# Power.net
KiCad netlist of a schematic drawn in Altium Designer
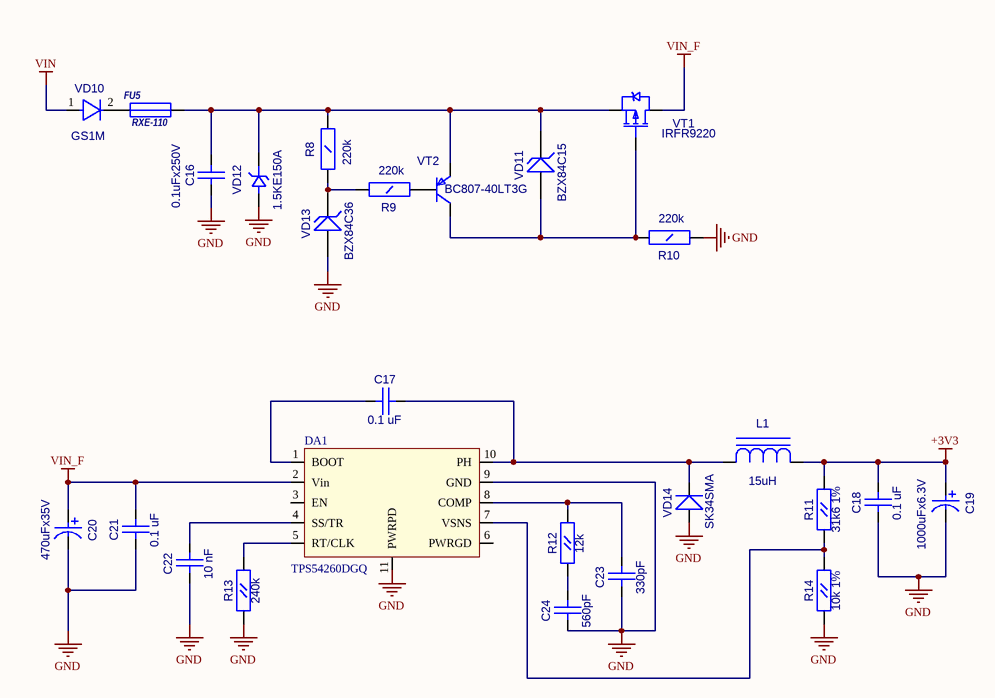
[diagram p0: Power.SchDoc]

(export (version "E")
  (design (tool "Eeschema 10.0.6"))
  (components
    (comp (ref "C16")
      (value "0.1uFx250V")
      (footprint "CC1206")
      (description "CC1206")
      (libsource (lib "gprs_modem_2") (part "CC1206"))
    )
    (comp (ref "C17")
      (value "0.1 uF")
      (footprint "CC0603")
      (description "CC0603")
      (libsource (lib "gprs_modem_2") (part "CC0603"))
    )
    (comp (ref "C18")
      (value "0.1 uF")
      (footprint "CC0603")
      (description "CC0603")
      (libsource (lib "gprs_modem_2") (part "CC0603"))
    )
    (comp (ref "C19")
      (value "1000uFx6.3V")
      (footprint "CC8X3.5")
      (description "CAP0.35")
      (libsource (lib "gprs_modem_2") (part "CAP0.35"))
    )
    (comp (ref "C20")
      (value "470uFx35V")
      (footprint "CC16X10_CAP0.5(1)(Primary)")
      (description "CAP0.5(1)")
      (libsource (lib "gprs_modem_2") (part "CAP0.5(1)"))
    )
    (comp (ref "C21")
      (value "0.1 uF")
      (footprint "CC0603")
      (description "CC0603")
      (libsource (lib "gprs_modem_2") (part "CC0603"))
    )
    (comp (ref "C22")
      (value "10 nF")
      (footprint "CC0603")
      (description "CC0603")
      (libsource (lib "gprs_modem_2") (part "CC0603"))
    )
    (comp (ref "C23")
      (value "330pF")
      (footprint "CC0603")
      (description "CC0603")
      (libsource (lib "gprs_modem_2") (part "CC0603"))
    )
    (comp (ref "C24")
      (value "560pF")
      (footprint "CC0603")
      (description "CC0603")
      (libsource (lib "gprs_modem_2") (part "CC0603"))
    )
    (comp (ref "DA1")
      (value "TPS54260DGQ")
      (footprint "S-PDSO-G10")
      (libsource (lib "gprs_modem") (part "TPS54260DGQ"))
    )
    (comp (ref "FU5")
      (value "RXE-110")
      (footprint "RXE-110")
      (libsource (lib "gprs_modem_2") (part "RXE-110"))
    )
    (comp (ref "L1")
      (value "15uH")
      (footprint "SDR0805")
      (description "SDR0805")
      (libsource (lib "gprs_modem") (part "SDR0805"))
    )
    (comp (ref "R8")
      (value "220k")
      (footprint "RC1206")
      (description "RC1206")
      (libsource (lib "gprs_modem_2") (part "RC1206"))
    )
    (comp (ref "R9")
      (value "220k")
      (footprint "RC1206")
      (description "RC1206")
      (libsource (lib "gprs_modem_2") (part "RC1206"))
    )
    (comp (ref "R10")
      (value "220k")
      (footprint "RC1206")
      (description "RC1206")
      (libsource (lib "gprs_modem_2") (part "RC1206"))
    )
    (comp (ref "R11")
      (value "31k6 1%")
      (footprint "RC0603")
      (description "RC0603")
      (libsource (lib "gprs_modem_2") (part "RC0603"))
    )
    (comp (ref "R12")
      (value "12k")
      (footprint "RC0603")
      (description "RC0603")
      (libsource (lib "gprs_modem_2") (part "RC0603"))
    )
    (comp (ref "R13")
      (value "240k")
      (footprint "RC0603")
      (description "RC0603")
      (libsource (lib "gprs_modem_2") (part "RC0603"))
    )
    (comp (ref "R14")
      (value "10k 1%")
      (footprint "RC0603")
      (description "RC0603")
      (libsource (lib "gprs_modem_2") (part "RC0603"))
    )
    (comp (ref "VD10") (value "GS1M") (footprint "SMA") (libsource (lib "Schetchik") (part "GS1M")))
    (comp (ref "VD11")
      (value "BZX84C15")
      (footprint "SOT-23(123)")
      (description "Zener Voltage Regulator Diode")
      (libsource (lib "gprs_modem_2") (part "BZX84"))
    )
    (comp (ref "VD12")
      (value "1.5KE150A")
      (footprint "DO-201")
      (description "1.5KE")
      (libsource (lib "gprs_modem") (part "1.5KE"))
    )
    (comp (ref "VD13")
      (value "BZX84C36")
      (footprint "SOT-23(123)")
      (description "Zener Voltage Regulator Diode")
      (libsource (lib "gprs_modem_2") (part "BZX84"))
    )
    (comp (ref "VD14")
      (value "SK34SMA")
      (footprint "SMA")
      (description "Schottky Rectifier")
      (libsource (lib "gprs_modem") (part "SK34SMA"))
    )
    (comp (ref "VT1")
      (value "IRFR9220")
      (footprint "D-PAK(TO-252AA)")
      (description "HEXFET Power MOSFET")
      (libsource (lib "gprs_modem") (part "IRFR9220"))
    )
    (comp (ref "VT2")
      (value "BC807-40LT3G")
      (footprint "SOT-23(123)")
      (description "BC856B")
      (libsource (lib "Schetchik") (part "BC856B"))
    )
  )
  (nets
    (net (code "1") (name "+3V3") (class "Default")
      (node (ref "C18") (pin "1") (pinfunction "A_1") (pintype "passive"))
      (node (ref "C19") (pin "1") (pintype "passive"))
      (node (ref "L1") (pin "2") (pinfunction "A_2") (pintype "passive"))
      (node (ref "R11") (pin "2") (pinfunction "B_2") (pintype "passive"))
    )
    (net (code "2") (name "GND") (class "Default")
      (node (ref "C16") (pin "1") (pinfunction "A_1") (pintype "passive"))
      (node (ref "C18") (pin "2") (pinfunction "B_2") (pintype "passive"))
      (node (ref "C19") (pin "2") (pintype "passive"))
      (node (ref "C20") (pin "1") (pintype "passive"))
      (node (ref "C21") (pin "2") (pinfunction "B_2") (pintype "passive"))
      (node (ref "C22") (pin "2") (pinfunction "B_2") (pintype "passive"))
      (node (ref "C23") (pin "2") (pinfunction "B_2") (pintype "passive"))
      (node (ref "C24") (pin "2") (pinfunction "B_2") (pintype "passive"))
      (node (ref "DA1") (pin "11") (pinfunction "PWRPD_11") (pintype "passive"))
      (node (ref "DA1") (pin "9") (pinfunction "GND_9") (pintype "passive"))
      (node (ref "R10") (pin "1") (pinfunction "A_1") (pintype "passive"))
      (node (ref "R13") (pin "1") (pinfunction "A_1") (pintype "passive"))
      (node (ref "R14") (pin "1") (pinfunction "A_1") (pintype "passive"))
      (node (ref "VD12") (pin "1") (pinfunction "A_1") (pintype "passive"))
      (node (ref "VD13") (pin "1") (pinfunction "A_1") (pintype "passive"))
      (node (ref "VD14") (pin "1") (pinfunction "A_1") (pintype "passive"))
    )
    (net (code "3") (name "Net-(C16-B)") (class "Default")
      (node (ref "C16") (pin "2") (pinfunction "B_2") (pintype "passive"))
      (node (ref "FU5") (pin "2") (pintype "passive"))
      (node (ref "R8") (pin "2") (pinfunction "B_2") (pintype "passive"))
      (node (ref "VD11") (pin "3") (pinfunction "K_3") (pintype "passive"))
      (node (ref "VD12") (pin "2") (pinfunction "K_2") (pintype "passive"))
      (node (ref "VT1") (pin "2") (pinfunction "S_2") (pintype "passive"))
      (node (ref "VT2") (pin "2") (pinfunction "E_2") (pintype "passive"))
    )
    (net (code "4") (name "Net-(C17-A)") (class "Default")
      (node (ref "C17") (pin "1") (pinfunction "A_1") (pintype "passive"))
      (node (ref "DA1") (pin "10") (pinfunction "PH_10") (pintype "passive"))
      (node (ref "L1") (pin "1") (pinfunction "C_1") (pintype "passive"))
      (node (ref "VD14") (pin "2") (pinfunction "K_2") (pintype "passive"))
    )
    (net (code "5") (name "Net-(C17-B)") (class "Default")
      (node (ref "C17") (pin "2") (pinfunction "B_2") (pintype "passive"))
      (node (ref "DA1") (pin "1") (pinfunction "BOOT_1") (pintype "passive"))
    )
    (net (code "6") (name "Net-(C22-A)") (class "Default")
      (node (ref "C22") (pin "1") (pinfunction "A_1") (pintype "passive"))
      (node (ref "DA1") (pin "4") (pinfunction "SS/TR_4") (pintype "passive"))
    )
    (net (code "7") (name "Net-(C23-A)") (class "Default")
      (node (ref "C23") (pin "1") (pinfunction "A_1") (pintype "passive"))
      (node (ref "DA1") (pin "8") (pinfunction "COMP_8") (pintype "passive"))
      (node (ref "R12") (pin "2") (pinfunction "B_2") (pintype "passive"))
    )
    (net (code "8") (name "Net-(C24-A)") (class "Default")
      (node (ref "C24") (pin "1") (pinfunction "A_1") (pintype "passive"))
      (node (ref "R12") (pin "1") (pinfunction "A_1") (pintype "passive"))
    )
    (net (code "9") (name "Net-(DA1-RT{slash}CLK)") (class "Default")
      (node (ref "DA1") (pin "5") (pinfunction "RT/CLK_5") (pintype "passive"))
      (node (ref "R13") (pin "2") (pinfunction "B_2") (pintype "passive"))
    )
    (net (code "10") (name "Net-(DA1-VSNS)") (class "Default")
      (node (ref "DA1") (pin "7") (pinfunction "VSNS_7") (pintype "passive"))
      (node (ref "R11") (pin "1") (pinfunction "A_1") (pintype "passive"))
      (node (ref "R14") (pin "2") (pinfunction "B_2") (pintype "passive"))
    )
    (net (code "11") (name "Net-(R8-A)") (class "Default")
      (node (ref "R8") (pin "1") (pinfunction "A_1") (pintype "passive"))
      (node (ref "R9") (pin "2") (pinfunction "B_2") (pintype "passive"))
      (node (ref "VD13") (pin "3") (pinfunction "K_3") (pintype "passive"))
    )
    (net (code "12") (name "Net-(R9-A)") (class "Default")
      (node (ref "R9") (pin "1") (pinfunction "A_1") (pintype "passive"))
      (node (ref "VT2") (pin "1") (pinfunction "B_1") (pintype "passive"))
    )
    (net (code "13") (name "Net-(R10-B)") (class "Default")
      (node (ref "R10") (pin "2") (pinfunction "B_2") (pintype "passive"))
      (node (ref "VD11") (pin "1") (pinfunction "A_1") (pintype "passive"))
      (node (ref "VT1") (pin "1") (pinfunction "G_1") (pintype "passive"))
      (node (ref "VT2") (pin "3") (pinfunction "C_3") (pintype "passive"))
    )
    (net (code "14") (name "Net-(VD10-K)") (class "Default")
      (node (ref "FU5") (pin "1") (pintype "passive"))
      (node (ref "VD10") (pin "2") (pinfunction "K_2") (pintype "passive"))
    )
    (net (code "15") (name "VIN") (class "Default")
      (node (ref "VD10") (pin "1") (pinfunction "A_1") (pintype "passive"))
    )
    (net (code "16") (name "VIN_F") (class "Default")
      (node (ref "C20") (pin "2") (pintype "passive"))
      (node (ref "C21") (pin "1") (pinfunction "A_1") (pintype "passive"))
      (node (ref "DA1") (pin "2") (pinfunction "Vin_2") (pintype "passive"))
      (node (ref "VT1") (pin "3") (pinfunction "D_3") (pintype "passive"))
    )
    (net (code "17") (name "unconnected-(DA1-EN-Pad3)") (class "Default")
      (node (ref "DA1") (pin "3") (pinfunction "EN_3") (pintype "passive"))
    )
    (net (code "18") (name "unconnected-(DA1-PWRGD-Pad6)") (class "Default")
      (node (ref "DA1") (pin "6") (pinfunction "PWRGD_6") (pintype "passive"))
    )
  )
)
